# 1_Interface.net
KiCad netlist of a schematic drawn in Altium Designer
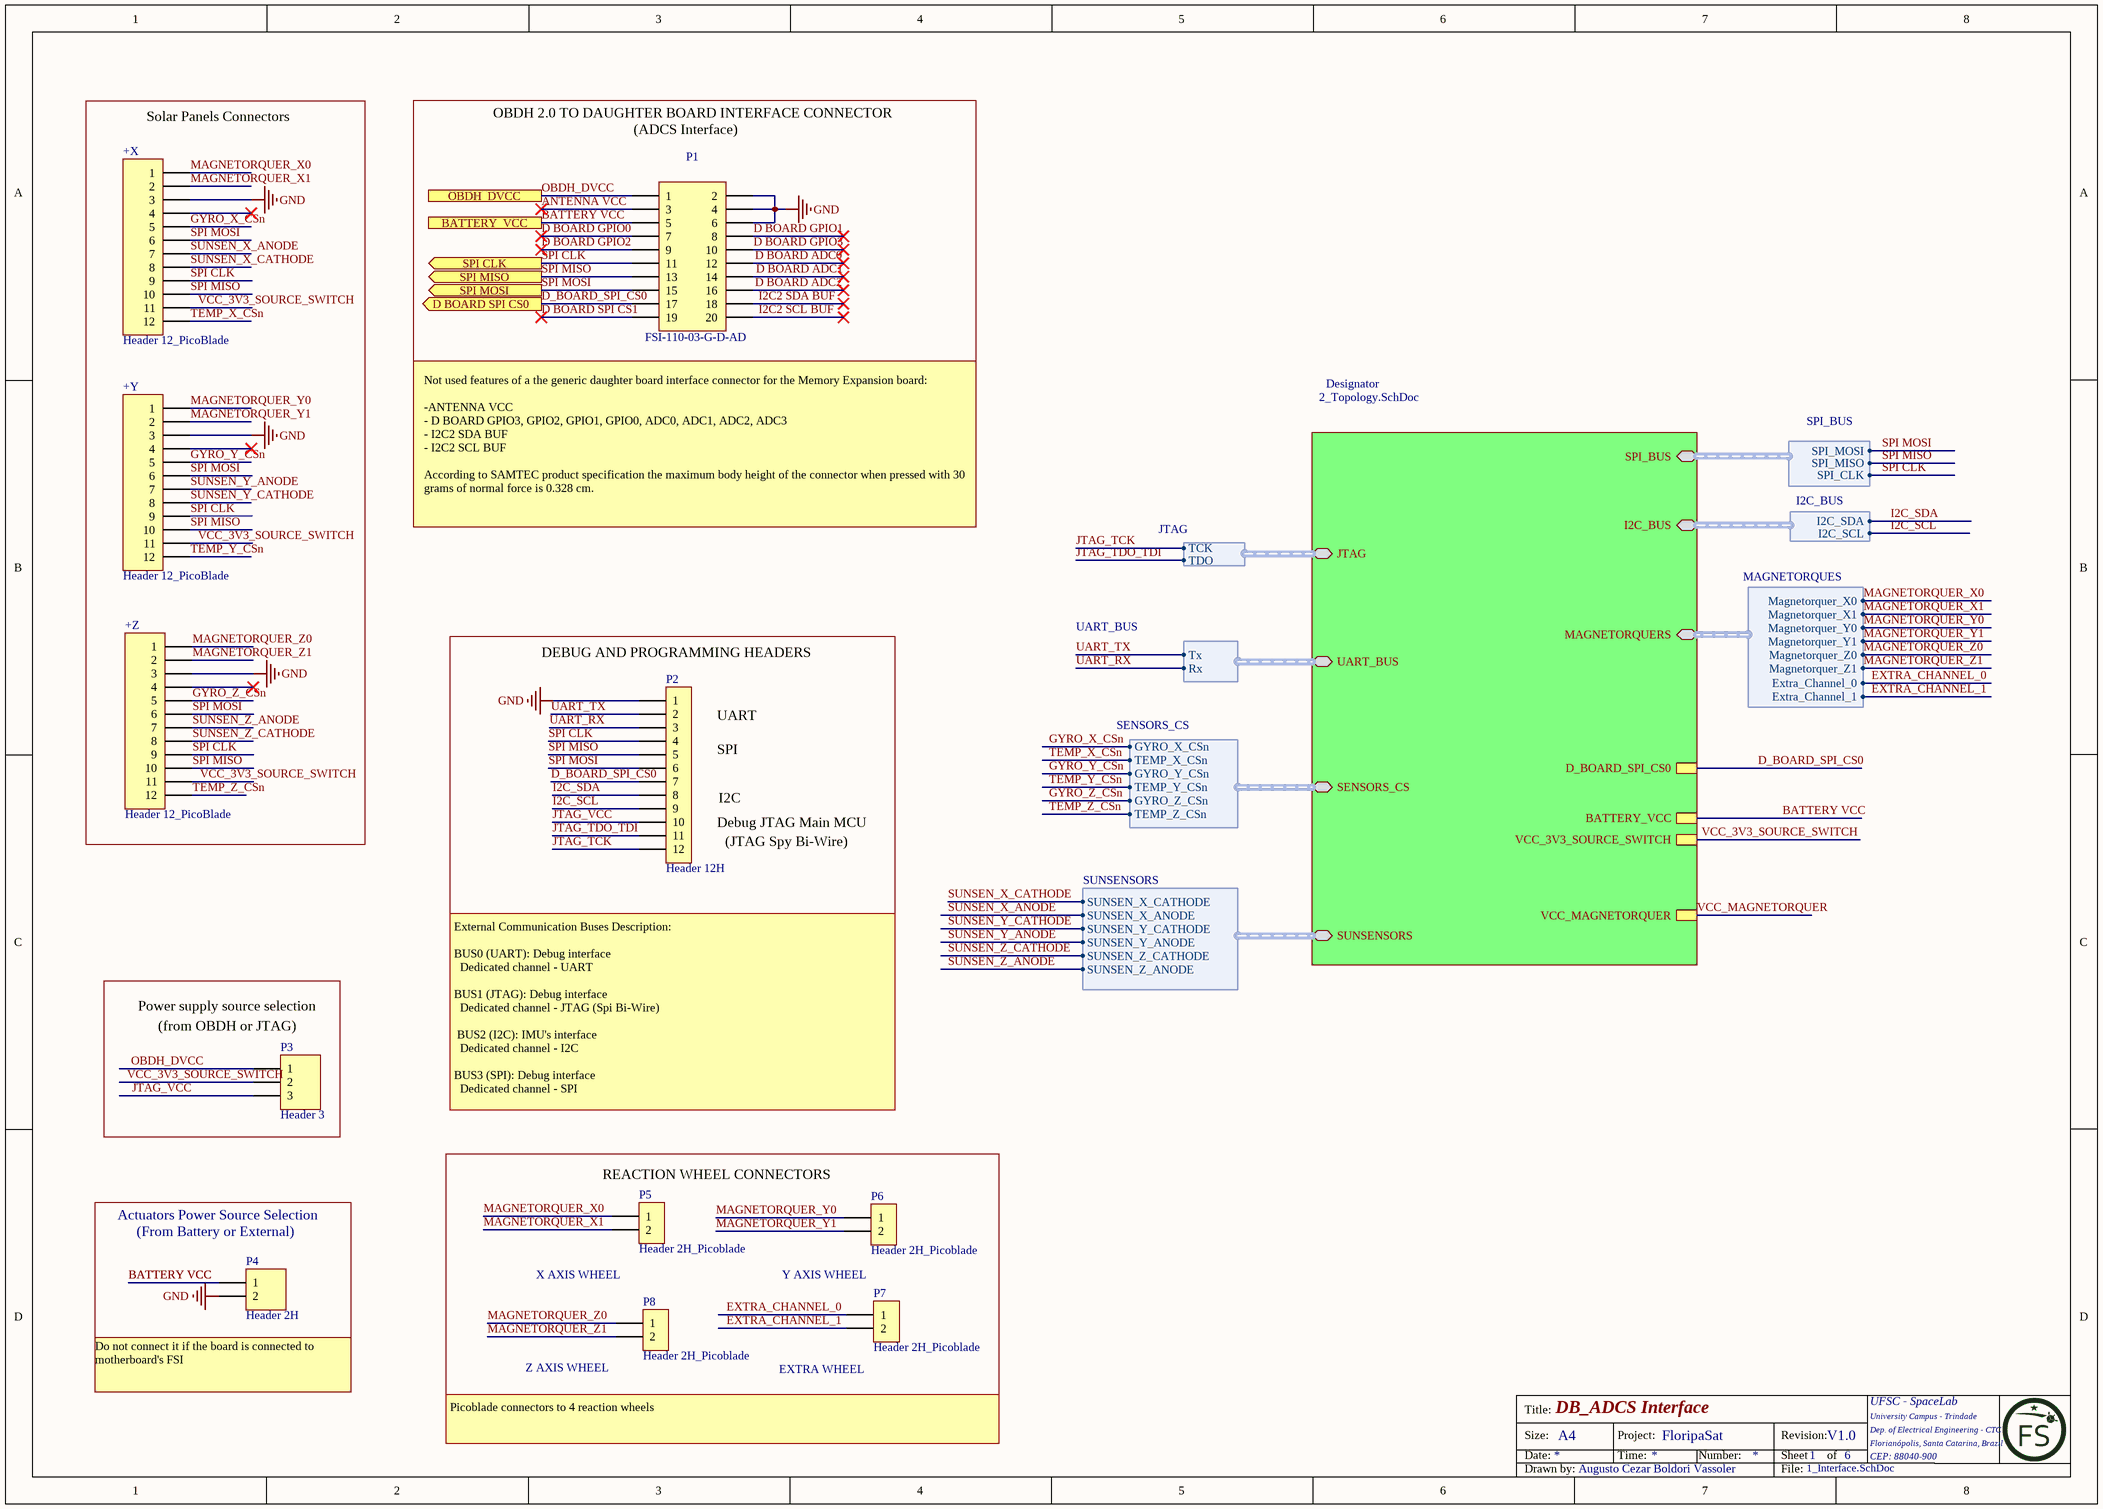
[diagram p0: 1_Interface.SchDoc]

(export (version "E")
  (design (tool "Eeschema 10.0.6"))
  (components
    (comp (ref "+X")
      (value "Header 12_PicoBlade")
      (footprint "HDR12 PicoBlade - duplicate")
      (description "Header, 12-Pin")
      (fields (field (name "PARTNUMBER") "53398-1271") (field (name "PUBLISHER") "Altium Limited"))
      (libsource (lib "FloripaSatSchlib") (part "Header 12_PicoBlade"))
    )
    (comp (ref "+Y")
      (value "Header 12_PicoBlade")
      (footprint "HDR12 PicoBlade - duplicate")
      (description "Header, 12-Pin")
      (fields (field (name "PARTNUMBER") "53398-1271") (field (name "PUBLISHER") "Altium Limited"))
      (libsource (lib "FloripaSatSchlib") (part "Header 12_PicoBlade"))
    )
    (comp (ref "+Z")
      (value "Header 12_PicoBlade")
      (footprint "HDR12 PicoBlade - duplicate")
      (description "Header, 12-Pin")
      (fields (field (name "PARTNUMBER") "533981271") (field (name "PUBLISHER") "Altium Limited"))
      (libsource (lib "FloripaSatSchlib") (part "Header 12_PicoBlade"))
    )
    (comp (ref "P1")
      (value "FSI-110-03-G-D-AD")
      (footprint "Mating FSI-110-03-G-D-AD")
      (description "CONN STACKING 20POS SMD GOLD")
      (fields (field (name "MANUFACTURER") "Samtec"))
      (libsource (lib "Memory_Expansion_Daughter_Board_SchLib") (part "FSI-110-03-G-D-AD"))
    )
    (comp (ref "P2")
      (value "Header 12H")
      (footprint "61301211021")
      (description "Header, 12")
      (fields
        (field (name "MANUFACTURER") "Wurth Electronics")
        (field (name "MANUFACTURER PART NUMBER") "61301211021")
      )
      (libsource (lib "PCB_DB_ADCS") (part "Header 12H"))
    )
    (comp (ref "P3")
      (value "Header 3")
      (footprint "HDR1X3")
      (description "Header, 3-Pin")
      (fields (field (name "PUBLISHER") "Altium Limited"))
      (libsource (lib "Miscellaneous Connectors") (part "Header 3"))
    )
    (comp (ref "P4")
      (value "Header 2H")
      (footprint "HDR1X2H")
      (description "Header, 2-Pin, Right Angle")
      (fields (field (name "PUBLISHER") "Altium Limited"))
      (libsource (lib "PCB_DB_ADCS") (part "Header 2H"))
    )
    (comp (ref "P5")
      (value "Header 2H_Picoblade")
      (footprint "HDR2 PICOBLADE")
      (description "Header,2-Pin,Right Angle")
      (fields (field (name "MANUFACTURER") "Molex") (field (name "MANUFACTURER PART NUMBER") "53261-0271"))
      (libsource (lib "PCB_DB_ADCS") (part "Header 2H_Picoblade"))
    )
    (comp (ref "P6")
      (value "Header 2H_Picoblade")
      (footprint "HDR2 PICOBLADE")
      (description "Header,2-Pin,Right Angle")
      (fields (field (name "MANUFACTURER") "Molex") (field (name "MANUFACTURER PART NUMBER") "53261-0271"))
      (libsource (lib "PCB_DB_ADCS") (part "Header 2H_Picoblade"))
    )
    (comp (ref "P7")
      (value "Header 2H_Picoblade")
      (footprint "HDR2 PICOBLADE")
      (description "Header,2-Pin,Right Angle")
      (fields (field (name "MANUFACTURER") "Molex") (field (name "MANUFACTURER PART NUMBER") "53261-0271"))
      (libsource (lib "PCB_DB_ADCS") (part "Header 2H_Picoblade"))
    )
    (comp (ref "P8")
      (value "Header 2H_Picoblade")
      (footprint "HDR2 PICOBLADE")
      (description "Header,2-Pin,Right Angle")
      (fields (field (name "MANUFACTURER") "Molex") (field (name "MANUFACTURER PART NUMBER") "53261-0271"))
      (libsource (lib "PCB_DB_ADCS") (part "Header 2H_Picoblade"))
    )
  )
  (nets
    (net (code "8") (name "/ANTENNA VCC") (class "Default")
      (node (ref "P1") (pin "3") (pinfunction "3_3") (pintype "passive+no_connect"))
    )
    (net (code "9") (name "/BATTERY VCC") (class "Default")
      (node (ref "P1") (pin "5") (pinfunction "5_5") (pintype "passive"))
      (node (ref "P4") (pin "1") (pinfunction "1_1") (pintype "passive"))
    )
    (net (code "10") (name "/D BOARD ADC0") (class "Default")
      (node (ref "P1") (pin "12") (pinfunction "12_12") (pintype "passive+no_connect"))
    )
    (net (code "11") (name "/D BOARD ADC1") (class "Default")
      (node (ref "P1") (pin "14") (pinfunction "14_14") (pintype "passive+no_connect"))
    )
    (net (code "12") (name "/D BOARD ADC2") (class "Default")
      (node (ref "P1") (pin "16") (pinfunction "16_16") (pintype "passive+no_connect"))
    )
    (net (code "13") (name "/D BOARD GPIO0") (class "Default")
      (node (ref "P1") (pin "7") (pinfunction "7_7") (pintype "passive+no_connect"))
    )
    (net (code "14") (name "/D BOARD GPIO1") (class "Default")
      (node (ref "P1") (pin "8") (pinfunction "8_8") (pintype "passive+no_connect"))
    )
    (net (code "15") (name "/D BOARD GPIO2") (class "Default")
      (node (ref "P1") (pin "9") (pinfunction "9_9") (pintype "passive+no_connect"))
    )
    (net (code "16") (name "/D BOARD GPIO3") (class "Default")
      (node (ref "P1") (pin "10") (pinfunction "10_10") (pintype "passive+no_connect"))
    )
    (net (code "17") (name "/D BOARD SPI CS1") (class "Default")
      (node (ref "P1") (pin "19") (pinfunction "19_19") (pintype "passive+no_connect"))
    )
    (net (code "18") (name "/D_BOARD_SPI_CS0") (class "Default")
      (node (ref "P1") (pin "17") (pinfunction "17_17") (pintype "passive"))
      (node (ref "P2") (pin "7") (pinfunction "7_7") (pintype "passive"))
    )
    (net (code "19") (name "/EXTRA_CHANNEL_0") (class "Default")
      (node (ref "P7") (pin "1") (pinfunction "1_1") (pintype "passive"))
    )
    (net (code "20") (name "/EXTRA_CHANNEL_1") (class "Default")
      (node (ref "P7") (pin "2") (pinfunction "2_2") (pintype "passive"))
    )
    (net (code "21") (name "/GYRO_X_CSn") (class "Default")
      (node (ref "+X") (pin "5") (pinfunction "5_5") (pintype "passive"))
    )
    (net (code "22") (name "/GYRO_Y_CSn") (class "Default")
      (node (ref "+Y") (pin "5") (pinfunction "5_5") (pintype "passive"))
    )
    (net (code "23") (name "/GYRO_Z_CSn") (class "Default")
      (node (ref "+Z") (pin "5") (pinfunction "5_5") (pintype "passive"))
    )
    (net (code "24") (name "/I2C2 SCL BUF") (class "Default")
      (node (ref "P1") (pin "20") (pinfunction "20_20") (pintype "passive+no_connect"))
    )
    (net (code "25") (name "/I2C2 SDA BUF") (class "Default")
      (node (ref "P1") (pin "18") (pinfunction "18_18") (pintype "passive+no_connect"))
    )
    (net (code "26") (name "/I2C_SCL") (class "Default")
      (node (ref "P2") (pin "9") (pinfunction "9_9") (pintype "passive"))
    )
    (net (code "27") (name "/I2C_SDA") (class "Default")
      (node (ref "P2") (pin "8") (pinfunction "8_8") (pintype "passive"))
    )
    (net (code "28") (name "/JTAG_TCK") (class "Default")
      (node (ref "P2") (pin "12") (pinfunction "12_12") (pintype "passive"))
    )
    (net (code "29") (name "/JTAG_TDO_TDI") (class "Default")
      (node (ref "P2") (pin "11") (pinfunction "11_11") (pintype "passive"))
    )
    (net (code "30") (name "/JTAG_VCC") (class "Default")
      (node (ref "P2") (pin "10") (pinfunction "10_10") (pintype "passive"))
      (node (ref "P3") (pin "3") (pinfunction "3_3") (pintype "passive"))
    )
    (net (code "31") (name "/MAGNETORQUER_X0") (class "Default")
      (node (ref "+X") (pin "1") (pinfunction "1_1") (pintype "passive"))
      (node (ref "P5") (pin "1") (pinfunction "1_1") (pintype "passive"))
    )
    (net (code "32") (name "/MAGNETORQUER_X1") (class "Default")
      (node (ref "+X") (pin "2") (pinfunction "2_2") (pintype "passive"))
      (node (ref "P5") (pin "2") (pinfunction "2_2") (pintype "passive"))
    )
    (net (code "33") (name "/MAGNETORQUER_Y0") (class "Default")
      (node (ref "+Y") (pin "1") (pinfunction "1_1") (pintype "passive"))
      (node (ref "P6") (pin "1") (pinfunction "1_1") (pintype "passive"))
    )
    (net (code "34") (name "/MAGNETORQUER_Y1") (class "Default")
      (node (ref "+Y") (pin "2") (pinfunction "2_2") (pintype "passive"))
      (node (ref "P6") (pin "2") (pinfunction "2_2") (pintype "passive"))
    )
    (net (code "35") (name "/MAGNETORQUER_Z0") (class "Default")
      (node (ref "+Z") (pin "1") (pinfunction "1_1") (pintype "passive"))
      (node (ref "P8") (pin "1") (pinfunction "1_1") (pintype "passive"))
    )
    (net (code "36") (name "/MAGNETORQUER_Z1") (class "Default")
      (node (ref "+Z") (pin "2") (pinfunction "2_2") (pintype "passive"))
      (node (ref "P8") (pin "2") (pinfunction "2_2") (pintype "passive"))
    )
    (net (code "37") (name "/OBDH_DVCC") (class "Default")
      (node (ref "P1") (pin "1") (pinfunction "1_1") (pintype "passive"))
      (node (ref "P3") (pin "1") (pinfunction "1_1") (pintype "passive"))
    )
    (net (code "38") (name "/SPI CLK") (class "Default")
      (node (ref "+X") (pin "9") (pinfunction "9_9") (pintype "passive"))
      (node (ref "+Y") (pin "9") (pinfunction "9_9") (pintype "passive"))
      (node (ref "+Z") (pin "9") (pinfunction "9_9") (pintype "passive"))
      (node (ref "P1") (pin "11") (pinfunction "11_11") (pintype "passive"))
      (node (ref "P2") (pin "4") (pinfunction "4_4") (pintype "passive"))
    )
    (net (code "39") (name "/SPI MISO") (class "Default")
      (node (ref "+X") (pin "10") (pinfunction "10_10") (pintype "passive"))
      (node (ref "+Y") (pin "10") (pinfunction "10_10") (pintype "passive"))
      (node (ref "+Z") (pin "10") (pinfunction "10_10") (pintype "passive"))
      (node (ref "P1") (pin "13") (pinfunction "13_13") (pintype "passive"))
      (node (ref "P2") (pin "5") (pinfunction "5_5") (pintype "passive"))
    )
    (net (code "40") (name "/SPI MOSI") (class "Default")
      (node (ref "+X") (pin "6") (pinfunction "6_6") (pintype "passive"))
      (node (ref "+Y") (pin "6") (pinfunction "6_6") (pintype "passive"))
      (node (ref "+Z") (pin "6") (pinfunction "6_6") (pintype "passive"))
      (node (ref "P1") (pin "15") (pinfunction "15_15") (pintype "passive"))
      (node (ref "P2") (pin "6") (pinfunction "6_6") (pintype "passive"))
    )
    (net (code "41") (name "/SUNSEN_X_ANODE") (class "Default")
      (node (ref "+X") (pin "7") (pinfunction "7_7") (pintype "passive"))
    )
    (net (code "42") (name "/SUNSEN_X_CATHODE") (class "Default")
      (node (ref "+X") (pin "8") (pinfunction "8_8") (pintype "passive"))
    )
    (net (code "43") (name "/SUNSEN_Y_ANODE") (class "Default")
      (node (ref "+Y") (pin "7") (pinfunction "7_7") (pintype "passive"))
    )
    (net (code "44") (name "/SUNSEN_Y_CATHODE") (class "Default")
      (node (ref "+Y") (pin "8") (pinfunction "8_8") (pintype "passive"))
    )
    (net (code "45") (name "/SUNSEN_Z_ANODE") (class "Default")
      (node (ref "+Z") (pin "7") (pinfunction "7_7") (pintype "passive"))
    )
    (net (code "46") (name "/SUNSEN_Z_CATHODE") (class "Default")
      (node (ref "+Z") (pin "8") (pinfunction "8_8") (pintype "passive"))
    )
    (net (code "47") (name "/TEMP_X_CSn") (class "Default")
      (node (ref "+X") (pin "12") (pinfunction "12_12") (pintype "passive"))
    )
    (net (code "48") (name "/TEMP_Y_CSn") (class "Default")
      (node (ref "+Y") (pin "12") (pinfunction "12_12") (pintype "passive"))
    )
    (net (code "49") (name "/TEMP_Z_CSn") (class "Default")
      (node (ref "+Z") (pin "12") (pinfunction "12_12") (pintype "passive"))
    )
    (net (code "50") (name "/UART_RX") (class "Default")
      (node (ref "P2") (pin "3") (pinfunction "3_3") (pintype "passive"))
    )
    (net (code "51") (name "/UART_TX") (class "Default")
      (node (ref "P2") (pin "2") (pinfunction "2_2") (pintype "passive"))
    )
    (net (code "52") (name "/VCC_3V3_SOURCE_SWITCH") (class "Default")
      (node (ref "+X") (pin "11") (pinfunction "11_11") (pintype "passive"))
      (node (ref "+Y") (pin "11") (pinfunction "11_11") (pintype "passive"))
      (node (ref "+Z") (pin "11") (pinfunction "11_11") (pintype "passive"))
      (node (ref "P3") (pin "2") (pinfunction "2_2") (pintype "passive"))
    )
    (net (code "61") (name "GND") (class "Default")
      (node (ref "+X") (pin "3") (pinfunction "3_3") (pintype "passive"))
      (node (ref "+Y") (pin "3") (pinfunction "3_3") (pintype "passive"))
      (node (ref "+Z") (pin "3") (pinfunction "3_3") (pintype "passive"))
      (node (ref "P1") (pin "2") (pinfunction "2_2") (pintype "passive"))
      (node (ref "P1") (pin "4") (pinfunction "4_4") (pintype "passive"))
      (node (ref "P1") (pin "6") (pinfunction "6_6") (pintype "passive"))
      (node (ref "P2") (pin "1") (pinfunction "1_1") (pintype "passive"))
      (node (ref "P4") (pin "2") (pinfunction "2_2") (pintype "passive"))
    )
    (net (code "62") (name "unconnected-(+X-Pad4)") (class "Default")
      (node (ref "+X") (pin "4") (pinfunction "4_4") (pintype "passive+no_connect"))
    )
    (net (code "63") (name "unconnected-(+Y-Pad4)") (class "Default")
      (node (ref "+Y") (pin "4") (pinfunction "4_4") (pintype "passive+no_connect"))
    )
    (net (code "64") (name "unconnected-(+Z-Pad4)") (class "Default")
      (node (ref "+Z") (pin "4") (pinfunction "4_4") (pintype "passive+no_connect"))
    )
  )
)
